# PanelWireGuide.net
KiCad netlist of a schematic drawn in EAGLE
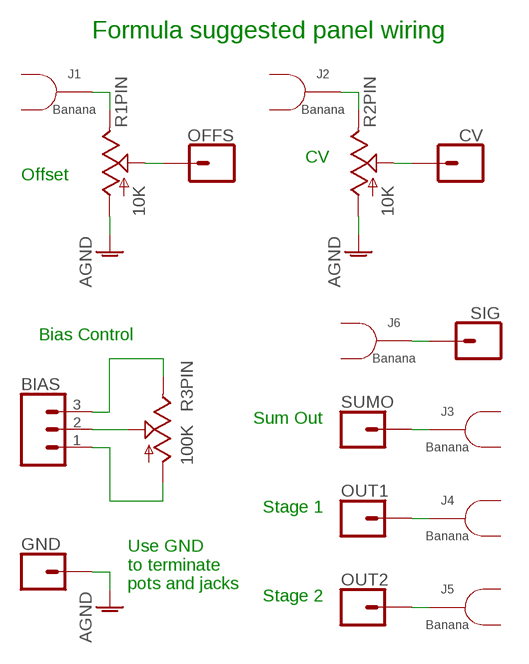
[diagram p0: schematic, sheet 1]

(export (version "E")
  (design (tool "Eeschema 10.0.6"))
  (components
    (comp (ref "BIAS")
      (value "3XWIREPAD")
      (footprint "eagle-import:1X03")
      (libsource (lib "eagle-import") (part "3XWIREPAD"))
    )
    (comp (ref "CV")
      (value "1XWIREPAD")
      (footprint "eagle-import:1X01")
      (libsource (lib "eagle-import") (part "1XWIREPAD"))
    )
    (comp (ref "GND")
      (value "1XWIREPAD")
      (footprint "eagle-import:1X01")
      (libsource (lib "eagle-import") (part "1XWIREPAD"))
    )
    (comp (ref "J1")
      (value "BANANA_SOCKET_PAD")
      (footprint "eagle-import:BANANA_PCB_PAD")
      (libsource (lib "eagle-import") (part "BANANA_SOCKET_PAD"))
    )
    (comp (ref "J2")
      (value "BANANA_SOCKET_PAD")
      (footprint "eagle-import:BANANA_PCB_PAD")
      (libsource (lib "eagle-import") (part "BANANA_SOCKET_PAD"))
    )
    (comp (ref "J3")
      (value "BANANA_SOCKET_PAD")
      (footprint "eagle-import:BANANA_PCB_PAD")
      (libsource (lib "eagle-import") (part "BANANA_SOCKET_PAD"))
    )
    (comp (ref "J4")
      (value "BANANA_SOCKET_PAD")
      (footprint "eagle-import:BANANA_PCB_PAD")
      (libsource (lib "eagle-import") (part "BANANA_SOCKET_PAD"))
    )
    (comp (ref "J5")
      (value "BANANA_SOCKET_PAD")
      (footprint "eagle-import:BANANA_PCB_PAD")
      (libsource (lib "eagle-import") (part "BANANA_SOCKET_PAD"))
    )
    (comp (ref "J6")
      (value "BANANA_SOCKET_PAD")
      (footprint "eagle-import:BANANA_PCB_PAD")
      (libsource (lib "eagle-import") (part "BANANA_SOCKET_PAD"))
    )
    (comp (ref "OFFS")
      (value "1XWIREPAD")
      (footprint "eagle-import:1X01")
      (libsource (lib "eagle-import") (part "1XWIREPAD"))
    )
    (comp (ref "OUT1")
      (value "1XWIREPAD")
      (footprint "eagle-import:1X01")
      (libsource (lib "eagle-import") (part "1XWIREPAD"))
    )
    (comp (ref "OUT2")
      (value "1XWIREPAD")
      (footprint "eagle-import:1X01")
      (libsource (lib "eagle-import") (part "1XWIREPAD"))
    )
    (comp (ref "R1")
      (value "10K")
      (footprint "eagle-import:ALPHA_RV09_9MMPOT")
      (libsource (lib "eagle-import") (part "POTENTIOMETER"))
    )
    (comp (ref "R2")
      (value "10K")
      (footprint "eagle-import:ALPHA_RV09_9MMPOT")
      (libsource (lib "eagle-import") (part "POTENTIOMETER"))
    )
    (comp (ref "R3")
      (value "100K")
      (footprint "eagle-import:ALPHA_RV09_9MMPOT")
      (libsource (lib "eagle-import") (part "POTENTIOMETER"))
    )
    (comp (ref "SIG")
      (value "1XWIREPAD")
      (footprint "eagle-import:1X01")
      (libsource (lib "eagle-import") (part "1XWIREPAD"))
    )
    (comp (ref "SUMO")
      (value "1XWIREPAD")
      (footprint "eagle-import:1X01")
      (libsource (lib "eagle-import") (part "1XWIREPAD"))
    )
  )
  (nets
    (net (code "1") (name "AGND") (class "Default")
      (node (ref "GND") (pin "1") (pinfunction "1_1") (pintype "passive"))
      (node (ref "R1") (pin "C1") (pinfunction "A_C1") (pintype "passive"))
      (node (ref "R2") (pin "C1") (pinfunction "A_C1") (pintype "passive"))
    )
    (net (code "2") (name "Net-(J1-P$1)") (class "Default")
      (node (ref "J1") (pin "P$2") (pinfunction "P$1_P$2") (pintype "bidirectional"))
      (node (ref "R1") (pin "C3") (pinfunction "B_C3") (pintype "passive"))
    )
    (net (code "3") (name "Net-(J2-P$1)") (class "Default")
      (node (ref "J2") (pin "P$2") (pinfunction "P$1_P$2") (pintype "bidirectional"))
      (node (ref "R2") (pin "C3") (pinfunction "B_C3") (pintype "passive"))
    )
    (net (code "4") (name "Net-(J3-P$1)") (class "Default")
      (node (ref "J3") (pin "P$2") (pinfunction "P$1_P$2") (pintype "bidirectional"))
      (node (ref "SUMO") (pin "1") (pinfunction "1_1") (pintype "passive"))
    )
    (net (code "5") (name "Net-(J4-P$1)") (class "Default")
      (node (ref "J4") (pin "P$2") (pinfunction "P$1_P$2") (pintype "bidirectional"))
      (node (ref "OUT1") (pin "1") (pinfunction "1_1") (pintype "passive"))
    )
    (net (code "6") (name "Net-(J5-P$1)") (class "Default")
      (node (ref "J5") (pin "P$2") (pinfunction "P$1_P$2") (pintype "bidirectional"))
      (node (ref "OUT2") (pin "1") (pinfunction "1_1") (pintype "passive"))
    )
    (net (code "7") (name "Net-(J6-P$1)") (class "Default")
      (node (ref "J6") (pin "P$2") (pinfunction "P$1_P$2") (pintype "bidirectional"))
      (node (ref "SIG") (pin "1") (pinfunction "1_1") (pintype "passive"))
    )
    (net (code "8") (name "Net-(R1B-W)") (class "Default")
      (node (ref "OFFS") (pin "1") (pinfunction "1_1") (pintype "passive"))
      (node (ref "R1") (pin "C2") (pinfunction "W_C2") (pintype "passive"))
    )
    (net (code "9") (name "Net-(R2B-W)") (class "Default")
      (node (ref "CV") (pin "1") (pinfunction "1_1") (pintype "passive"))
      (node (ref "R2") (pin "C2") (pinfunction "W_C2") (pintype "passive"))
    )
    (net (code "10") (name "Net-(R3B-A)") (class "Default")
      (node (ref "BIAS") (pin "1") (pinfunction "1_1") (pintype "passive"))
      (node (ref "R3") (pin "C1") (pinfunction "A_C1") (pintype "passive"))
    )
    (net (code "11") (name "Net-(R3B-B)") (class "Default")
      (node (ref "BIAS") (pin "3") (pinfunction "3_3") (pintype "passive"))
      (node (ref "R3") (pin "C3") (pinfunction "B_C3") (pintype "passive"))
    )
    (net (code "12") (name "Net-(R3B-W)") (class "Default")
      (node (ref "BIAS") (pin "2") (pinfunction "2_2") (pintype "passive"))
      (node (ref "R3") (pin "C2") (pinfunction "W_C2") (pintype "passive"))
    )
  )
)
